# PA_Schem.net
KiCad netlist of a schematic drawn in Altium Designer
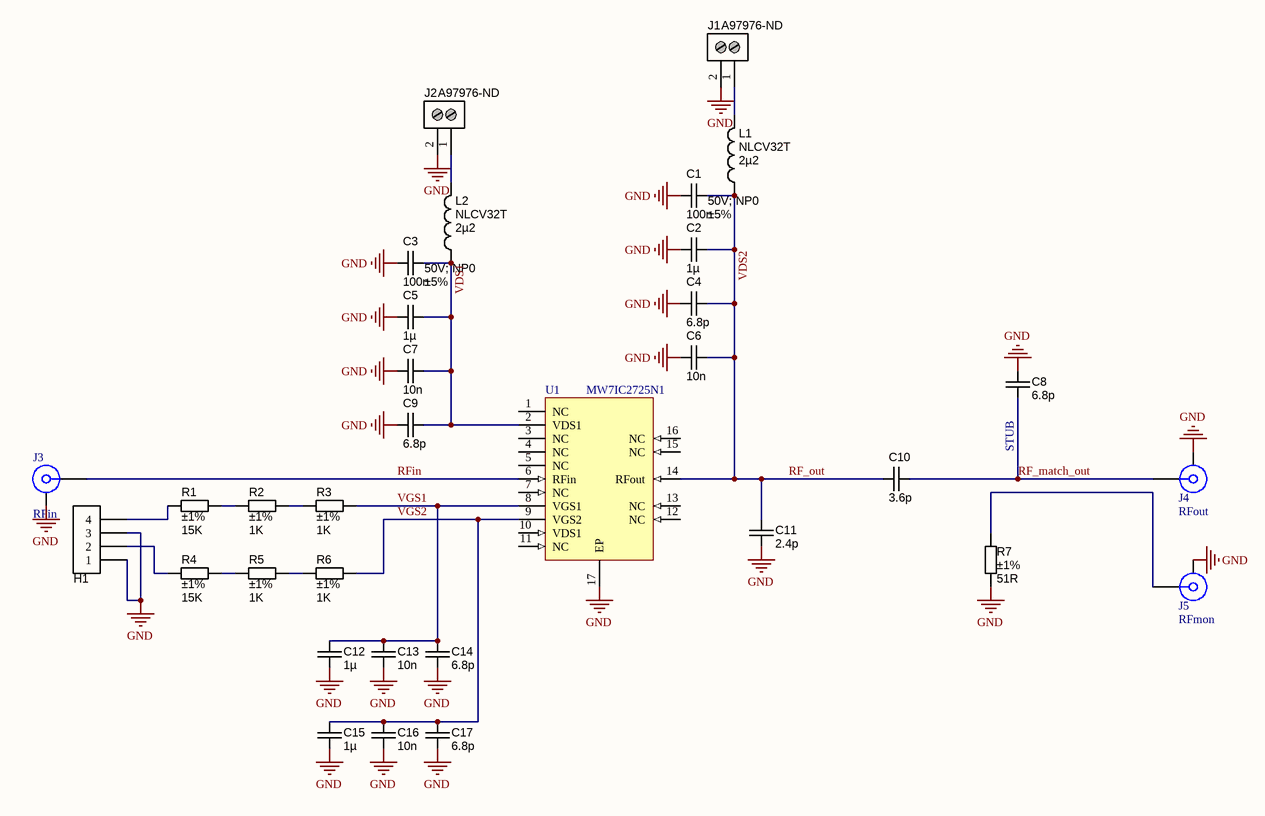
[diagram p0: PA_Schem.SchDoc]

(export (version "E")
  (design (tool "Eeschema 10.0.6"))
  (components
    (comp (ref "C1")
      (value "100n")
      (footprint "CAPC3216X180N")
      (description "Capacitor SMD Cer 100nF 1206 NP0 50V 5%")
      (fields (field (name "TOLERANCE") "±5%") (field (name "RATINGS") "50V; NP0"))
      (libsource (lib "PBL - Capacitors") (part "CAPC_100n_1206_NP0_50V_5%"))
    )
    (comp (ref "C2")
      (value "1µ")
      (footprint "CAPC1608X90N")
      (description "Capacitor SMD Cer 1uF 10% 16V X7R 0603")
      (fields (field (name "TOLERANCE") "±10%") (field (name "Comment") "approved sub OK"))
      (libsource (lib "PBL - Capacitors") (part "CAPC_1u_0603_X7R_16V_10%"))
    )
    (comp (ref "C3")
      (value "100n")
      (footprint "CAPC3216X180N")
      (description "Capacitor SMD Cer 100nF 1206 NP0 50V 5%")
      (fields (field (name "TOLERANCE") "±5%") (field (name "RATINGS") "50V; NP0"))
      (libsource (lib "PBL - Capacitors") (part "CAPC_100n_1206_NP0_50V_5%"))
    )
    (comp (ref "C4")
      (value "6.8p")
      (footprint "CAPC1608X90N")
      (description "Capacitor SMD Cer 8pF ±0.5pF 50V NP0 0603")
      (fields (field (name "TOLERANCE") "±0.5pF"))
      (libsource (lib "PBL - Capacitors") (part "CAPC_8p_0603_NP0_50V"))
    )
    (comp (ref "C5")
      (value "1µ")
      (footprint "CAPC1608X90N")
      (description "Capacitor SMD Cer 1uF 10% 16V X7R 0603")
      (fields (field (name "TOLERANCE") "±10%") (field (name "Comment") "approved sub OK"))
      (libsource (lib "PBL - Capacitors") (part "CAPC_1u_0603_X7R_16V_10%"))
    )
    (comp (ref "C6")
      (value "10n")
      (footprint "CAPC1608X90N")
      (description "Capacitor SMD Cer 10nF 10% 100V X7R 0603")
      (fields
        (field (name "TOLERANCE") "±10%")
        (field (name "MANUFACTURER") "Murata Electronics North America")
      )
      (libsource (lib "PBL - Capacitors") (part "CAPC_10n_0603_X7R_100V_10%"))
    )
    (comp (ref "C7")
      (value "10n")
      (footprint "CAPC1608X90N")
      (description "Capacitor SMD Cer 10nF 10% 100V X7R 0603")
      (fields
        (field (name "TOLERANCE") "±10%")
        (field (name "MANUFACTURER") "Murata Electronics North America")
      )
      (libsource (lib "PBL - Capacitors") (part "CAPC_10n_0603_X7R_100V_10%"))
    )
    (comp (ref "C8")
      (value "6.8p")
      (footprint "CAPC1608X90N")
      (description "Capacitor SMD Cer 8pF ±0.5pF 50V NP0 0603")
      (fields (field (name "TOLERANCE") "±0.5pF"))
      (libsource (lib "PBL - Capacitors") (part "CAPC_8p_0603_NP0_50V"))
    )
    (comp (ref "C9")
      (value "6.8p")
      (footprint "CAPC1608X90N")
      (description "Capacitor SMD Cer 8pF ±0.5pF 50V NP0 0603")
      (fields (field (name "TOLERANCE") "±0.5pF"))
      (libsource (lib "PBL - Capacitors") (part "CAPC_8p_0603_NP0_50V"))
    )
    (comp (ref "C10")
      (value "3.6p")
      (footprint "CAPC1608X90N")
      (description "Capacitor SMD Cer 8pF ±0.5pF 50V NP0 0603")
      (fields (field (name "TOLERANCE") "±0.5pF"))
      (libsource (lib "PBL - Capacitors") (part "CAPC_8p_0603_NP0_50V"))
    )
    (comp (ref "C11")
      (value "2.4p")
      (footprint "CAPC1608X90N")
      (description "Capacitor SMD Cer 8pF ±0.5pF 50V NP0 0603")
      (fields (field (name "TOLERANCE") "±0.5pF"))
      (libsource (lib "PBL - Capacitors") (part "CAPC_8p_0603_NP0_50V"))
    )
    (comp (ref "C12")
      (value "1µ")
      (footprint "CAPC1608X90N")
      (description "Capacitor SMD Cer 1uF 10% 16V X7R 0603")
      (fields (field (name "TOLERANCE") "±10%") (field (name "Comment") "approved sub OK"))
      (libsource (lib "PBL - Capacitors") (part "CAPC_1u_0603_X7R_16V_10%"))
    )
    (comp (ref "C13")
      (value "10n")
      (footprint "CAPC1608X90N")
      (description "Capacitor SMD Cer 10nF 10% 100V X7R 0603")
      (fields
        (field (name "TOLERANCE") "±10%")
        (field (name "MANUFACTURER") "Murata Electronics North America")
      )
      (libsource (lib "PBL - Capacitors") (part "CAPC_10n_0603_X7R_100V_10%"))
    )
    (comp (ref "C14")
      (value "6.8p")
      (footprint "CAPC1608X90N")
      (description "Capacitor SMD Cer 8pF ±0.5pF 50V NP0 0603")
      (fields (field (name "TOLERANCE") "±0.5pF"))
      (libsource (lib "PBL - Capacitors") (part "CAPC_8p_0603_NP0_50V"))
    )
    (comp (ref "C15")
      (value "1µ")
      (footprint "CAPC1608X90N")
      (description "Capacitor SMD Cer 1uF 10% 16V X7R 0603")
      (fields (field (name "TOLERANCE") "±10%") (field (name "Comment") "approved sub OK"))
      (libsource (lib "PBL - Capacitors") (part "CAPC_1u_0603_X7R_16V_10%"))
    )
    (comp (ref "C16")
      (value "10n")
      (footprint "CAPC1608X90N")
      (description "Capacitor SMD Cer 10nF 10% 100V X7R 0603")
      (fields
        (field (name "TOLERANCE") "±10%")
        (field (name "MANUFACTURER") "Murata Electronics North America")
      )
      (libsource (lib "PBL - Capacitors") (part "CAPC_10n_0603_X7R_100V_10%"))
    )
    (comp (ref "C17")
      (value "6.8p")
      (footprint "CAPC1608X90N")
      (description "Capacitor SMD Cer 8pF ±0.5pF 50V NP0 0603")
      (fields (field (name "TOLERANCE") "±0.5pF"))
      (libsource (lib "PBL - Capacitors") (part "CAPC_8p_0603_NP0_50V"))
    )
    (comp (ref "H1")
      (value "Programmer")
      (footprint "HDR1X4_2.54MMP")
      (description "Header 4-pin")
      (libsource (lib "PBL - Connectors") (part "Header4P"))
    )
    (comp (ref "J1")
      (value "Stackable ScrewTerm")
      (footprint "2P_PCB_ScrewTerm_90S_3.81MM")
      (description "Terminal Block Screw Type THT 2-Position 3.81mm pitch")
      (fields (field (name "SUPPLIER PART NUMBER 1") "A97976-ND"))
      (libsource (lib "PBL - Connectors") (part "2P_ScrewTerm_90S_3.81MM"))
    )
    (comp (ref "J2")
      (value "Stackable ScrewTerm")
      (footprint "2P_PCB_ScrewTerm_90S_3.81MM")
      (description "Terminal Block Screw Type THT 2-Position 3.81mm pitch")
      (fields (field (name "SUPPLIER PART NUMBER 1") "A97976-ND"))
      (libsource (lib "PBL - Connectors") (part "2P_ScrewTerm_90S_3.81MM"))
    )
    (comp (ref "J3")
      (value "RFin")
      (footprint "ROS-32K145-400L5_V")
      (description "SMA Right Angle Jack, Edge Mount, Up to 18 GHz, -55 to 155 degC")
      (fields (field (name "PARTNUMBER") "32K145-400L5"))
      (libsource (lib "Rosenberger SMA") (part "32K145-400L5"))
    )
    (comp (ref "J4")
      (value "RFout")
      (footprint "ROS-32K145-400L5_V")
      (description "SMA Right Angle Jack, Edge Mount, Up to 18 GHz, -55 to 155 degC")
      (fields (field (name "PARTNUMBER") "32K145-400L5"))
      (libsource (lib "Rosenberger SMA") (part "32K145-400L5"))
    )
    (comp (ref "J5")
      (value "RFmon")
      (footprint "ROS-32K145-400L5_V")
      (description "SMA Right Angle Jack, Edge Mount, Up to 18 GHz, -55 to 155 degC")
      (fields (field (name "PARTNUMBER") "32K145-400L5"))
      (libsource (lib "Rosenberger SMA") (part "32K145-400L5"))
    )
    (comp (ref "L1")
      (value "NLCV32T")
      (footprint "INDM3225X240N")
      (description "Inductor 2.2uH 1.2A 1210 SMD chip")
      (fields (field (name "TOLERANCE") "±20%") (field (name "ALTIUM_VALUE") "2µ2"))
      (libsource (lib "PBL - Inductors") (part "INDC_2u2_1210_1200mA"))
    )
    (comp (ref "L2")
      (value "NLCV32T")
      (footprint "INDM3225X240N")
      (description "Inductor 2.2uH 1.2A 1210 SMD chip")
      (fields (field (name "TOLERANCE") "±20%") (field (name "ALTIUM_VALUE") "2µ2"))
      (libsource (lib "PBL - Inductors") (part "INDC_2u2_1210_1200mA"))
    )
    (comp (ref "R1")
      (value "15K")
      (footprint "RESC1608X55N")
      (description "Resistor SMD chip 15k Ohm 0.1W 1% 0603")
      (fields (field (name "TOLERANCE") "±1%") (field (name "Comment") "Thick Film"))
      (libsource (lib "PBL - Resistors") (part "RES_15K_0603_1%"))
    )
    (comp (ref "R2")
      (value "1K")
      (footprint "RESC1608X55N")
      (description "Resistor SMD chip 1k Ohm 0.1W 1% 0603")
      (fields (field (name "TOLERANCE") "±1%") (field (name "Comment") "Thick Film"))
      (libsource (lib "PBL - Resistors") (part "RES_1K_0603_1%"))
    )
    (comp (ref "R3")
      (value "1K")
      (footprint "RESC1608X55N")
      (description "Resistor SMD chip 1k Ohm 0.1W 1% 0603")
      (fields (field (name "TOLERANCE") "±1%") (field (name "Comment") "Thick Film"))
      (libsource (lib "PBL - Resistors") (part "RES_1K_0603_1%"))
    )
    (comp (ref "R4")
      (value "15K")
      (footprint "RESC1608X55N")
      (description "Resistor SMD chip 15k Ohm 0.1W 1% 0603")
      (fields (field (name "TOLERANCE") "±1%") (field (name "Comment") "Thick Film"))
      (libsource (lib "PBL - Resistors") (part "RES_15K_0603_1%"))
    )
    (comp (ref "R5")
      (value "1K")
      (footprint "RESC1608X55N")
      (description "Resistor SMD chip 1k Ohm 0.1W 1% 0603")
      (fields (field (name "TOLERANCE") "±1%") (field (name "Comment") "Thick Film"))
      (libsource (lib "PBL - Resistors") (part "RES_1K_0603_1%"))
    )
    (comp (ref "R6")
      (value "1K")
      (footprint "RESC1608X55N")
      (description "Resistor SMD chip 1k Ohm 0.1W 1% 0603")
      (fields (field (name "TOLERANCE") "±1%") (field (name "Comment") "Thick Film"))
      (libsource (lib "PBL - Resistors") (part "RES_1K_0603_1%"))
    )
    (comp (ref "R7")
      (value "51R")
      (footprint "RESC1608X55N")
      (description "Resistor SMD chip 51 Ohm 0.1W 1% 0603")
      (fields (field (name "TOLERANCE") "±1%") (field (name "Comment") "Thick Film"))
      (libsource (lib "PBL - Resistors") (part "RES_51R_0603_1%"))
    )
    (comp (ref "U1")
      (value "MW7IC2725N1")
      (footprint "CFP102P1410X258-16N")
      (libsource (lib "MW7IC2725N") (part "MW7IC2725N1"))
    )
  )
  (nets
    (net (code "1") (name "/RF_match_out") (class "Default")
      (node (ref "C10") (pin "1") (pintype "passive"))
      (node (ref "C8") (pin "2") (pintype "passive"))
      (node (ref "J4") (pin "1") (pinfunction "1_1") (pintype "passive"))
    )
    (net (code "2") (name "/RF_out") (class "Default")
      (node (ref "C1") (pin "2") (pintype "passive"))
      (node (ref "C10") (pin "2") (pintype "passive"))
      (node (ref "C11") (pin "1") (pintype "passive"))
      (node (ref "C2") (pin "1") (pintype "passive"))
      (node (ref "C4") (pin "1") (pintype "passive"))
      (node (ref "C6") (pin "1") (pintype "passive"))
      (node (ref "L1") (pin "1") (pinfunction "1_1") (pintype "passive"))
      (node (ref "U1") (pin "14") (pinfunction "RFout_14") (pintype "input"))
    )
    (net (code "3") (name "/RFin") (class "Default")
      (node (ref "J3") (pin "1") (pinfunction "1_1") (pintype "passive"))
      (node (ref "U1") (pin "6") (pinfunction "RFin_6") (pintype "input"))
    )
    (net (code "4") (name "/VDS1") (class "Default")
      (node (ref "C3") (pin "2") (pintype "passive"))
      (node (ref "C5") (pin "1") (pintype "passive"))
      (node (ref "C7") (pin "1") (pintype "passive"))
      (node (ref "C9") (pin "1") (pintype "passive"))
      (node (ref "L2") (pin "1") (pinfunction "1_1") (pintype "passive"))
      (node (ref "U1") (pin "2") (pinfunction "VDS1_2") (pintype "power_in"))
    )
    (net (code "5") (name "/VGS1") (class "Default")
      (node (ref "C12") (pin "1") (pintype "passive"))
      (node (ref "C13") (pin "1") (pintype "passive"))
      (node (ref "C14") (pin "1") (pintype "passive"))
      (node (ref "R3") (pin "2") (pinfunction "2_2") (pintype "passive"))
      (node (ref "U1") (pin "8") (pinfunction "VGS1_8") (pintype "power_in"))
    )
    (net (code "6") (name "/VGS2") (class "Default")
      (node (ref "C15") (pin "1") (pintype "passive"))
      (node (ref "C16") (pin "1") (pintype "passive"))
      (node (ref "C17") (pin "1") (pintype "passive"))
      (node (ref "R6") (pin "2") (pinfunction "2_2") (pintype "passive"))
      (node (ref "U1") (pin "9") (pinfunction "VGS2_9") (pintype "power_in"))
    )
    (net (code "7") (name "GND") (class "Default")
      (node (ref "C1") (pin "1") (pintype "passive"))
      (node (ref "C11") (pin "2") (pintype "passive"))
      (node (ref "C12") (pin "2") (pintype "passive"))
      (node (ref "C13") (pin "2") (pintype "passive"))
      (node (ref "C14") (pin "2") (pintype "passive"))
      (node (ref "C15") (pin "2") (pintype "passive"))
      (node (ref "C16") (pin "2") (pintype "passive"))
      (node (ref "C17") (pin "2") (pintype "passive"))
      (node (ref "C2") (pin "2") (pintype "passive"))
      (node (ref "C3") (pin "1") (pintype "passive"))
      (node (ref "C4") (pin "2") (pintype "passive"))
      (node (ref "C5") (pin "2") (pintype "passive"))
      (node (ref "C6") (pin "2") (pintype "passive"))
      (node (ref "C7") (pin "2") (pintype "passive"))
      (node (ref "C8") (pin "1") (pintype "passive"))
      (node (ref "C9") (pin "2") (pintype "passive"))
      (node (ref "H1") (pin "1") (pinfunction "1_1") (pintype "passive"))
      (node (ref "H1") (pin "3") (pinfunction "3_3") (pintype "passive"))
      (node (ref "J1") (pin "2") (pinfunction "2_2") (pintype "passive"))
      (node (ref "J2") (pin "2") (pinfunction "2_2") (pintype "passive"))
      (node (ref "J3") (pin "MP") (pinfunction "MP_MP") (pintype "passive"))
      (node (ref "J4") (pin "MP") (pinfunction "MP_MP") (pintype "passive"))
      (node (ref "J5") (pin "MP") (pinfunction "MP_MP") (pintype "passive"))
      (node (ref "R7") (pin "2") (pinfunction "2_2") (pintype "passive"))
      (node (ref "U1") (pin "17") (pinfunction "EP_17") (pintype "passive"))
    )
    (net (code "8") (name "Net-(H1-Pad2)") (class "Default")
      (node (ref "H1") (pin "2") (pinfunction "2_2") (pintype "passive"))
      (node (ref "R4") (pin "1") (pinfunction "1_1") (pintype "passive"))
    )
    (net (code "9") (name "Net-(H1-Pad4)") (class "Default")
      (node (ref "H1") (pin "4") (pinfunction "4_4") (pintype "passive"))
      (node (ref "R1") (pin "1") (pinfunction "1_1") (pintype "passive"))
    )
    (net (code "10") (name "Net-(J1-Pad1)") (class "Default")
      (node (ref "J1") (pin "1") (pinfunction "1_1") (pintype "passive"))
      (node (ref "L1") (pin "2") (pinfunction "2_2") (pintype "passive"))
    )
    (net (code "11") (name "Net-(J2-Pad1)") (class "Default")
      (node (ref "J2") (pin "1") (pinfunction "1_1") (pintype "passive"))
      (node (ref "L2") (pin "2") (pinfunction "2_2") (pintype "passive"))
    )
    (net (code "12") (name "Net-(J5-Pad1)") (class "Default")
      (node (ref "J5") (pin "1") (pinfunction "1_1") (pintype "passive"))
      (node (ref "R7") (pin "1") (pinfunction "1_1") (pintype "passive"))
    )
    (net (code "13") (name "Net-(R1-Pad2)") (class "Default")
      (node (ref "R1") (pin "2") (pinfunction "2_2") (pintype "passive"))
      (node (ref "R2") (pin "1") (pinfunction "1_1") (pintype "passive"))
    )
    (net (code "14") (name "Net-(R2-Pad2)") (class "Default")
      (node (ref "R2") (pin "2") (pinfunction "2_2") (pintype "passive"))
      (node (ref "R3") (pin "1") (pinfunction "1_1") (pintype "passive"))
    )
    (net (code "15") (name "Net-(R4-Pad2)") (class "Default")
      (node (ref "R4") (pin "2") (pinfunction "2_2") (pintype "passive"))
      (node (ref "R5") (pin "1") (pinfunction "1_1") (pintype "passive"))
    )
    (net (code "16") (name "Net-(R5-Pad2)") (class "Default")
      (node (ref "R5") (pin "2") (pinfunction "2_2") (pintype "passive"))
      (node (ref "R6") (pin "1") (pinfunction "1_1") (pintype "passive"))
    )
    (net (code "17") (name "unconnected-(U1-NC-Pad1)") (class "Default")
      (node (ref "U1") (pin "1") (pinfunction "NC_1") (pintype "tri_state"))
    )
    (net (code "18") (name "unconnected-(U1-NC-Pad3)") (class "Default")
      (node (ref "U1") (pin "3") (pinfunction "NC_3") (pintype "tri_state"))
    )
    (net (code "19") (name "unconnected-(U1-NC-Pad4)") (class "Default")
      (node (ref "U1") (pin "4") (pinfunction "NC_4") (pintype "tri_state"))
    )
    (net (code "20") (name "unconnected-(U1-NC-Pad5)") (class "Default")
      (node (ref "U1") (pin "5") (pinfunction "NC_5") (pintype "tri_state"))
    )
    (net (code "21") (name "unconnected-(U1-NC-Pad7)") (class "Default")
      (node (ref "U1") (pin "7") (pinfunction "NC_7") (pintype "input"))
    )
    (net (code "22") (name "unconnected-(U1-NC-Pad11)") (class "Default")
      (node (ref "U1") (pin "11") (pinfunction "NC_11") (pintype "input"))
    )
    (net (code "23") (name "unconnected-(U1-NC-Pad12)") (class "Default")
      (node (ref "U1") (pin "12") (pinfunction "NC_12") (pintype "input"))
    )
    (net (code "24") (name "unconnected-(U1-NC-Pad13)") (class "Default")
      (node (ref "U1") (pin "13") (pinfunction "NC_13") (pintype "input"))
    )
    (net (code "25") (name "unconnected-(U1-NC-Pad15)") (class "Default")
      (node (ref "U1") (pin "15") (pinfunction "NC_15") (pintype "input"))
    )
    (net (code "26") (name "unconnected-(U1-NC-Pad16)") (class "Default")
      (node (ref "U1") (pin "16") (pinfunction "NC_16") (pintype "input"))
    )
    (net (code "27") (name "unconnected-(U1-VDS1-Pad10)") (class "Default")
      (node (ref "U1") (pin "10") (pinfunction "VDS1_10") (pintype "input"))
    )
  )
)
